# 3_3v_BUCK.net
KiCad netlist of a schematic drawn in Altium Designer
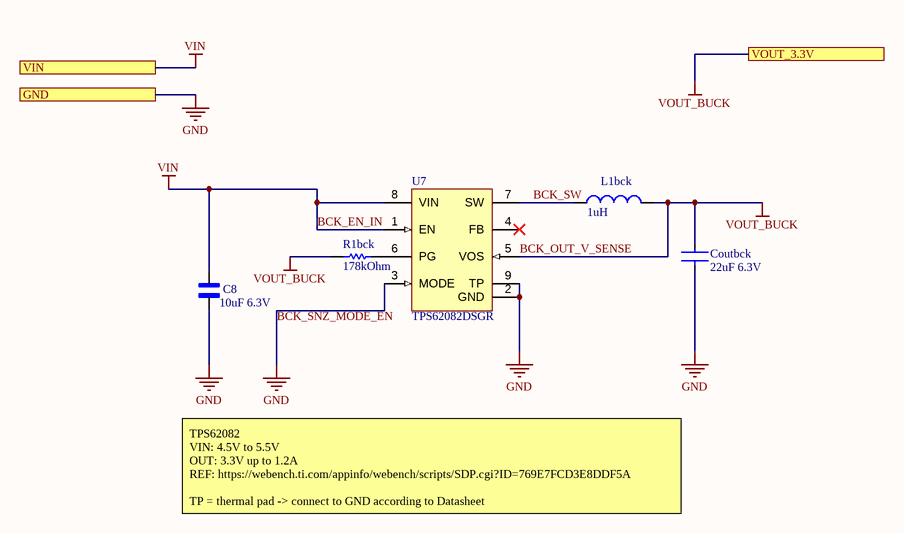
[diagram p0: 3.3v_BUCK.SchDoc]

(export (version "E")
  (design (tool "Eeschema 10.0.6"))
  (components
    (comp (ref "C8")
      (value "10uF 6.3V")
      (footprint "GRJ155R60J106ME11D")
      (description "Capacitor Ceramic Mlcc 0402 10UF 6.3V SMD")
      (fields
        (field (name "MANUFACTURER") "Murata")
        (field (name "MANUFACTURER PART NUMBER") "GRJ155R60J106ME11D")
      )
      (libsource (lib "CommonComponents_DIY") (part "GRJ155R60J106ME11D"))
    )
    (comp (ref "Coutbck")
      (value "22uF 6.3V")
      (footprint "FP-GRM188-0_2-IPC_B")
      (fields (field (name "TOLERANCE") "20%"))
      (libsource (lib "Altium Content Vault") (part "11868f565c42a9108669ba33697ecf6"))
    )
    (comp (ref "L1bck")
      (value "1uH")
      (footprint "WE-HCI-7040")
      (description "SMD Flat Wire High Current Inductor WE-HCI, L=1.00 µH 744311100")
      (libsource (lib "Altium Content Vault") (part "PAS-IND-INDUCTOR-2"))
    )
    (comp (ref "R1bck")
      (value "178kOhm")
      (footprint "RESC1608X55X25NL10T15")
      (description "RC0603FR-07178KL")
      (fields (field (name "MANUFACTURER") "Yageo"))
      (libsource (lib "Altium Content Vault") (part "RES"))
    )
    (comp (ref "U7")
      (value "TPS62082DSGR")
      (footprint "DSG8-1600X900TP")
      (fields (field (name "MANUFACTURER") "Texas Instruments"))
      (libsource (lib "Altium Content Vault") (part "TI-TPS62082DSG8-1600X900TP"))
    )
  )
  (nets
    (net (code "1") (name "/BCK_SW") (class "Default")
      (node (ref "L1bck") (pin "1") (pinfunction "1_1") (pintype "passive"))
      (node (ref "U7") (pin "7") (pinfunction "SW_7") (pintype "power_in"))
    )
    (net (code "2") (name "GND") (class "Default")
      (node (ref "C8") (pin "1") (pinfunction "1_1") (pintype "passive"))
      (node (ref "Coutbck") (pin "1") (pinfunction "1_1") (pintype "passive"))
      (node (ref "U7") (pin "2") (pinfunction "GND_2") (pintype "power_in"))
      (node (ref "U7") (pin "3") (pinfunction "MODE_3") (pintype "input"))
      (node (ref "U7") (pin "9") (pinfunction "TP_9") (pintype "power_in"))
    )
    (net (code "3") (name "Net-(U7-PG)") (class "Default")
      (node (ref "R1bck") (pin "2") (pinfunction "2_2") (pintype "passive"))
      (node (ref "U7") (pin "6") (pinfunction "PG_6") (pintype "tri_state"))
    )
    (net (code "4") (name "VIN") (class "Default")
      (node (ref "C8") (pin "2") (pinfunction "2_2") (pintype "passive"))
      (node (ref "U7") (pin "1") (pinfunction "EN_1") (pintype "input"))
      (node (ref "U7") (pin "8") (pinfunction "VIN_8") (pintype "power_in"))
    )
    (net (code "5") (name "VOUT_BUCK") (class "Default")
      (node (ref "Coutbck") (pin "2") (pinfunction "2_2") (pintype "passive"))
      (node (ref "L1bck") (pin "2") (pinfunction "2_2") (pintype "passive"))
      (node (ref "R1bck") (pin "1") (pinfunction "1_1") (pintype "passive"))
      (node (ref "U7") (pin "5") (pinfunction "VOS_5") (pintype "input"))
    )
    (net (code "6") (name "unconnected-(U7-FB-Pad4)") (class "Default")
      (node (ref "U7") (pin "4") (pinfunction "FB_4") (pintype "passive+no_connect"))
    )
  )
)
